# PWM_1_1.net
KiCad netlist of a schematic drawn in EAGLE
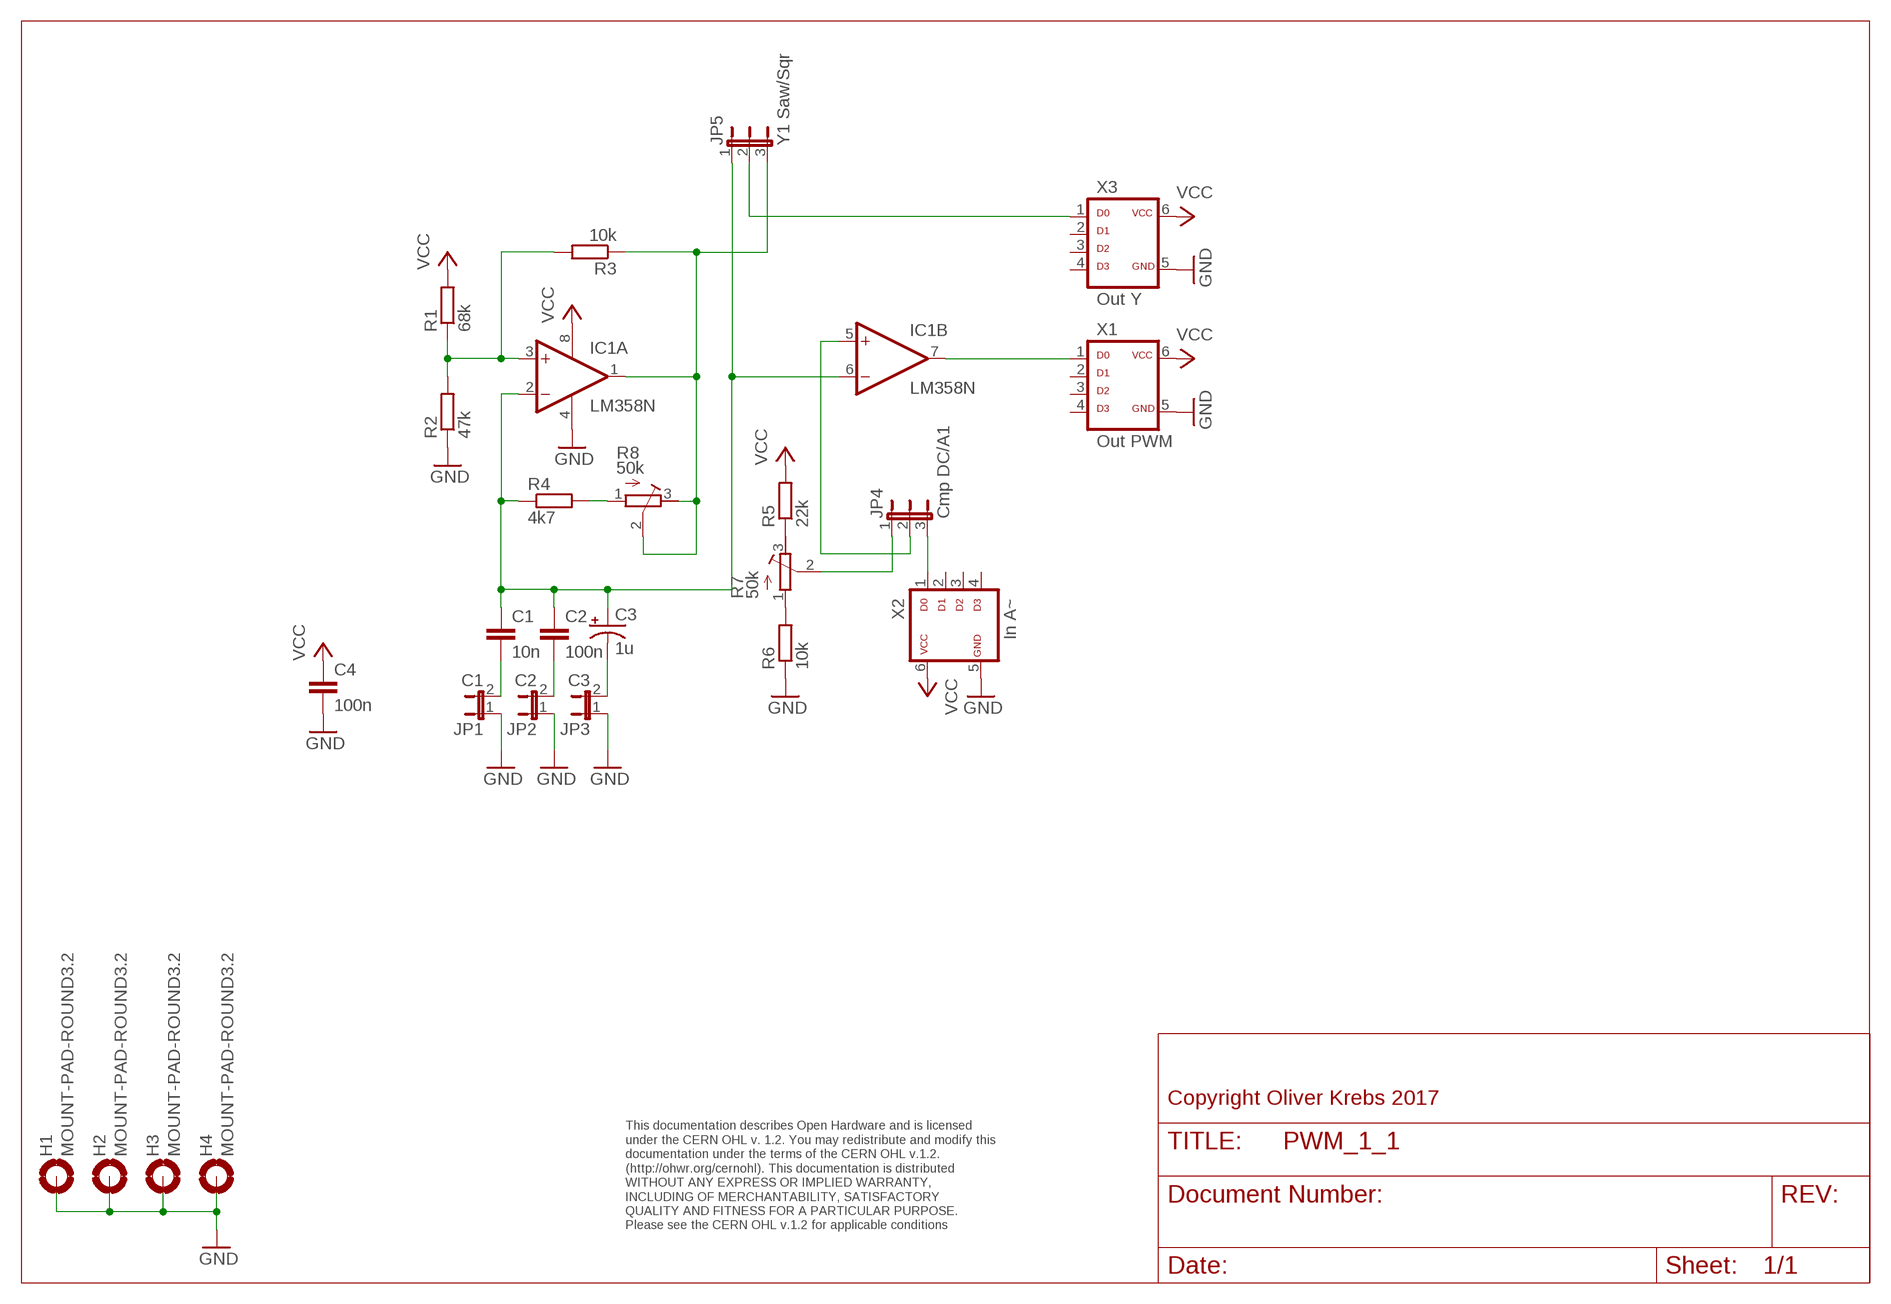
[diagram p0: schematic, sheet 1]

(export (version "E")
  (design (tool "Eeschema 10.0.6"))
  (components
    (comp (ref "C1")
      (value "10n")
      (footprint "eagle-import:C050-025X075")
      (libsource (lib "eagle-import") (part "C-EU050-025X075"))
    )
    (comp (ref "C2")
      (value "100n")
      (footprint "eagle-import:C050-025X075")
      (libsource (lib "eagle-import") (part "C-EU050-025X075"))
    )
    (comp (ref "C3")
      (value "1u")
      (footprint "eagle-import:CPOL-RADIAL-10UF-25V")
      (libsource (lib "eagle-import") (part "CAP_POLPTH2"))
    )
    (comp (ref "C4")
      (value "100n")
      (footprint "eagle-import:C050-025X075")
      (libsource (lib "eagle-import") (part "C-EU050-025X075"))
    )
    (comp (ref "H1")
      (value "MOUNT-PAD-ROUND3.2")
      (footprint "eagle-import:3,2-PAD")
      (libsource (lib "eagle-import") (part "MOUNT-PAD-ROUND3.2"))
    )
    (comp (ref "H2")
      (value "MOUNT-PAD-ROUND3.2")
      (footprint "eagle-import:3,2-PAD")
      (libsource (lib "eagle-import") (part "MOUNT-PAD-ROUND3.2"))
    )
    (comp (ref "H3")
      (value "MOUNT-PAD-ROUND3.2")
      (footprint "eagle-import:3,2-PAD")
      (libsource (lib "eagle-import") (part "MOUNT-PAD-ROUND3.2"))
    )
    (comp (ref "H4")
      (value "MOUNT-PAD-ROUND3.2")
      (footprint "eagle-import:3,2-PAD")
      (libsource (lib "eagle-import") (part "MOUNT-PAD-ROUND3.2"))
    )
    (comp (ref "IC1")
      (value "LM358N")
      (footprint "eagle-import:DIL08")
      (libsource (lib "eagle-import") (part "LM358N"))
    )
    (comp (ref "JP1")
      (value "C1")
      (footprint "eagle-import:JP1")
      (libsource (lib "eagle-import") (part "JP1E"))
    )
    (comp (ref "JP2")
      (value "C2")
      (footprint "eagle-import:JP1")
      (libsource (lib "eagle-import") (part "JP1E"))
    )
    (comp (ref "JP3")
      (value "C3")
      (footprint "eagle-import:JP1")
      (libsource (lib "eagle-import") (part "JP1E"))
    )
    (comp (ref "JP4")
      (value "Cmp DC/A1")
      (footprint "eagle-import:JP2-U")
      (libsource (lib "eagle-import") (part "JP2EJP2-U"))
    )
    (comp (ref "JP5")
      (value "Y1 Saw/Sqr")
      (footprint "eagle-import:JP2-U")
      (libsource (lib "eagle-import") (part "JP2EJP2-U"))
    )
    (comp (ref "R1")
      (value "68k")
      (footprint "eagle-import:0207_10")
      (libsource (lib "eagle-import") (part "R-EU_0207/10"))
    )
    (comp (ref "R2")
      (value "47k")
      (footprint "eagle-import:0207_10")
      (libsource (lib "eagle-import") (part "R-EU_0207/10"))
    )
    (comp (ref "R3")
      (value "10k")
      (footprint "eagle-import:0207_10")
      (libsource (lib "eagle-import") (part "R-EU_0207/10"))
    )
    (comp (ref "R4")
      (value "4k7")
      (footprint "eagle-import:0207_10")
      (libsource (lib "eagle-import") (part "R-EU_0207/10"))
    )
    (comp (ref "R5")
      (value "22k")
      (footprint "eagle-import:0207_10")
      (libsource (lib "eagle-import") (part "R-EU_0207/10"))
    )
    (comp (ref "R6")
      (value "10k")
      (footprint "eagle-import:0207_10")
      (libsource (lib "eagle-import") (part "R-EU_0207/10"))
    )
    (comp (ref "R7")
      (value "50k")
      (footprint "eagle-import:ACP-6L")
      (libsource (lib "eagle-import") (part "R-TRIMMACP"))
    )
    (comp (ref "R8")
      (value "50k")
      (footprint "eagle-import:ACP-6L")
      (libsource (lib "eagle-import") (part "R-TRIMMACP"))
    )
    (comp (ref "X1")
      (value "Out PWM")
      (footprint "eagle-import:ML-6")
      (libsource (lib "eagle-import") (part "ML6D"))
    )
    (comp (ref "X2")
      (value "In A~")
      (footprint "eagle-import:ML-6")
      (libsource (lib "eagle-import") (part "ML6D"))
    )
    (comp (ref "X3")
      (value "Out Y")
      (footprint "eagle-import:ML-6")
      (libsource (lib "eagle-import") (part "ML6D"))
    )
  )
  (nets
    (net (code "1") (name "GND") (class "Default")
      (node (ref "C4") (pin "2") (pinfunction "2_2") (pintype "passive"))
      (node (ref "H1") (pin "B3,2") (pinfunction "MOUNT_B3,2") (pintype "passive"))
      (node (ref "H2") (pin "B3,2") (pinfunction "MOUNT_B3,2") (pintype "passive"))
      (node (ref "H3") (pin "B3,2") (pinfunction "MOUNT_B3,2") (pintype "passive"))
      (node (ref "H4") (pin "B3,2") (pinfunction "MOUNT_B3,2") (pintype "passive"))
      (node (ref "IC1") (pin "4") (pinfunction "V-_4") (pintype "power_in"))
      (node (ref "JP1") (pin "1") (pinfunction "1_1") (pintype "passive"))
      (node (ref "JP2") (pin "1") (pinfunction "1_1") (pintype "passive"))
      (node (ref "JP3") (pin "1") (pinfunction "1_1") (pintype "passive"))
      (node (ref "R2") (pin "1") (pinfunction "1_1") (pintype "passive"))
      (node (ref "R6") (pin "1") (pinfunction "1_1") (pintype "passive"))
      (node (ref "X1") (pin "5") (pinfunction "5_5") (pintype "passive"))
      (node (ref "X2") (pin "5") (pinfunction "5_5") (pintype "passive"))
      (node (ref "X3") (pin "5") (pinfunction "5_5") (pintype "passive"))
    )
    (net (code "2") (name "Net-(C1-Pad2)") (class "Default")
      (node (ref "C1") (pin "2") (pinfunction "2_2") (pintype "passive"))
      (node (ref "JP1") (pin "2") (pinfunction "2_2") (pintype "passive"))
    )
    (net (code "3") (name "Net-(C2-Pad2)") (class "Default")
      (node (ref "C2") (pin "2") (pinfunction "2_2") (pintype "passive"))
      (node (ref "JP2") (pin "2") (pinfunction "2_2") (pintype "passive"))
    )
    (net (code "4") (name "Net-(C3-+)") (class "Default")
      (node (ref "C1") (pin "1") (pinfunction "1_1") (pintype "passive"))
      (node (ref "C2") (pin "1") (pinfunction "1_1") (pintype "passive"))
      (node (ref "C3") (pin "1") (pinfunction "+_1") (pintype "passive"))
      (node (ref "IC1") (pin "2") (pinfunction "-IN_2") (pintype "input"))
      (node (ref "IC1") (pin "6") (pinfunction "-IN_6") (pintype "input"))
      (node (ref "JP5") (pin "1") (pinfunction "1_1") (pintype "passive"))
      (node (ref "R4") (pin "1") (pinfunction "1_1") (pintype "passive"))
    )
    (net (code "5") (name "Net-(C3--)") (class "Default")
      (node (ref "C3") (pin "2") (pinfunction "-_2") (pintype "passive"))
      (node (ref "JP3") (pin "2") (pinfunction "2_2") (pintype "passive"))
    )
    (net (code "6") (name "Net-(IC1A-+IN)") (class "Default")
      (node (ref "IC1") (pin "3") (pinfunction "+IN_3") (pintype "input"))
      (node (ref "R1") (pin "1") (pinfunction "1_1") (pintype "passive"))
      (node (ref "R2") (pin "2") (pinfunction "2_2") (pintype "passive"))
      (node (ref "R3") (pin "2") (pinfunction "2_2") (pintype "passive"))
    )
    (net (code "7") (name "Net-(IC1A-OUT)") (class "Default")
      (node (ref "IC1") (pin "1") (pinfunction "OUT_1") (pintype "output"))
      (node (ref "JP5") (pin "3") (pinfunction "3_3") (pintype "passive"))
      (node (ref "R3") (pin "1") (pinfunction "1_1") (pintype "passive"))
      (node (ref "R8") (pin "2") (pinfunction "S_2") (pintype "passive"))
      (node (ref "R8") (pin "3") (pinfunction "E_3") (pintype "passive"))
    )
    (net (code "8") (name "Net-(IC1B-+IN)") (class "Default")
      (node (ref "IC1") (pin "5") (pinfunction "+IN_5") (pintype "input"))
      (node (ref "JP4") (pin "2") (pinfunction "2_2") (pintype "passive"))
    )
    (net (code "9") (name "Net-(IC1B-OUT)") (class "Default")
      (node (ref "IC1") (pin "7") (pinfunction "OUT_7") (pintype "output"))
      (node (ref "X1") (pin "1") (pinfunction "1_1") (pintype "passive"))
    )
    (net (code "10") (name "Net-(JP4-Pad3)") (class "Default")
      (node (ref "JP4") (pin "3") (pinfunction "3_3") (pintype "passive"))
      (node (ref "X2") (pin "1") (pinfunction "1_1") (pintype "passive"))
    )
    (net (code "11") (name "Net-(JP5-Pad2)") (class "Default")
      (node (ref "JP5") (pin "2") (pinfunction "2_2") (pintype "passive"))
      (node (ref "X3") (pin "1") (pinfunction "1_1") (pintype "passive"))
    )
    (net (code "12") (name "Net-(R7-A)") (class "Default")
      (node (ref "R6") (pin "2") (pinfunction "2_2") (pintype "passive"))
      (node (ref "R7") (pin "1") (pinfunction "A_1") (pintype "passive"))
    )
    (net (code "13") (name "Net-(R7-E)") (class "Default")
      (node (ref "R5") (pin "1") (pinfunction "1_1") (pintype "passive"))
      (node (ref "R7") (pin "3") (pinfunction "E_3") (pintype "passive"))
    )
    (net (code "14") (name "Net-(R7-S)") (class "Default")
      (node (ref "JP4") (pin "1") (pinfunction "1_1") (pintype "passive"))
      (node (ref "R7") (pin "2") (pinfunction "S_2") (pintype "passive"))
    )
    (net (code "15") (name "Net-(R8-A)") (class "Default")
      (node (ref "R4") (pin "2") (pinfunction "2_2") (pintype "passive"))
      (node (ref "R8") (pin "1") (pinfunction "A_1") (pintype "passive"))
    )
    (net (code "16") (name "VCC") (class "Default")
      (node (ref "C4") (pin "1") (pinfunction "1_1") (pintype "passive"))
      (node (ref "IC1") (pin "8") (pinfunction "V+_8") (pintype "power_in"))
      (node (ref "R1") (pin "2") (pinfunction "2_2") (pintype "passive"))
      (node (ref "R5") (pin "2") (pinfunction "2_2") (pintype "passive"))
      (node (ref "X1") (pin "6") (pinfunction "6_6") (pintype "passive"))
      (node (ref "X2") (pin "6") (pinfunction "6_6") (pintype "passive"))
      (node (ref "X3") (pin "6") (pinfunction "6_6") (pintype "passive"))
    )
    (net (code "17") (name "unconnected-(X1-Pad2)") (class "Default")
      (node (ref "X1") (pin "2") (pinfunction "2_2") (pintype "passive"))
    )
    (net (code "18") (name "unconnected-(X1-Pad3)") (class "Default")
      (node (ref "X1") (pin "3") (pinfunction "3_3") (pintype "passive"))
    )
    (net (code "19") (name "unconnected-(X1-Pad4)") (class "Default")
      (node (ref "X1") (pin "4") (pinfunction "4_4") (pintype "passive"))
    )
    (net (code "20") (name "unconnected-(X2-Pad2)") (class "Default")
      (node (ref "X2") (pin "2") (pinfunction "2_2") (pintype "passive"))
    )
    (net (code "21") (name "unconnected-(X2-Pad3)") (class "Default")
      (node (ref "X2") (pin "3") (pinfunction "3_3") (pintype "passive"))
    )
    (net (code "22") (name "unconnected-(X2-Pad4)") (class "Default")
      (node (ref "X2") (pin "4") (pinfunction "4_4") (pintype "passive"))
    )
    (net (code "23") (name "unconnected-(X3-Pad2)") (class "Default")
      (node (ref "X3") (pin "2") (pinfunction "2_2") (pintype "passive"))
    )
    (net (code "24") (name "unconnected-(X3-Pad3)") (class "Default")
      (node (ref "X3") (pin "3") (pinfunction "3_3") (pintype "passive"))
    )
    (net (code "25") (name "unconnected-(X3-Pad4)") (class "Default")
      (node (ref "X3") (pin "4") (pinfunction "4_4") (pintype "passive"))
    )
  )
)
